# Motor_Module.net
KiCad netlist of a schematic drawn in Altium Designer
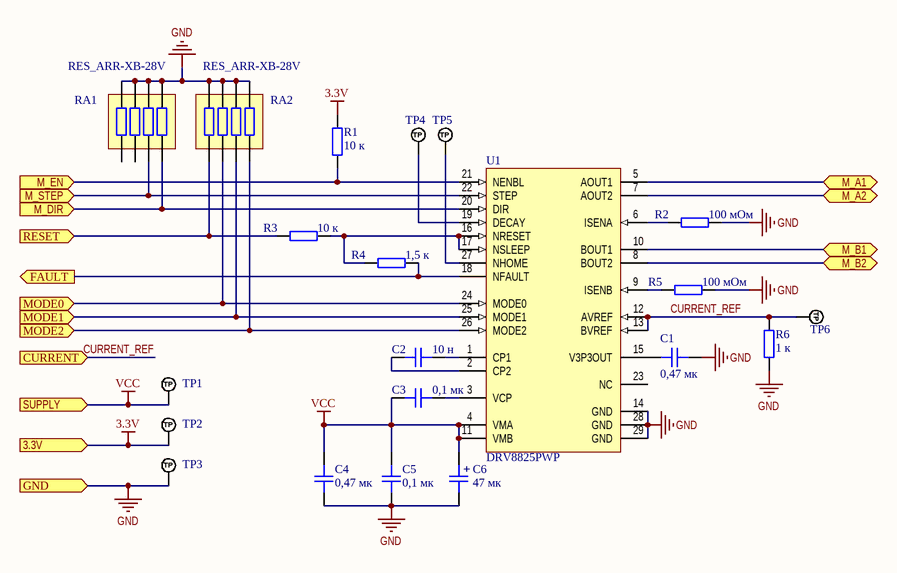
[diagram p0: Motor_Module.SchDoc]

(export (version "E")
  (design (tool "Eeschema 10.0.6"))
  (components
    (comp (ref "C1")
      (value "0,47 мк")
      (footprint "CAP_0603")
      (description "Capacitor SMD 0805")
      (libsource (lib "Schematic-Lib-PhilsLab") (part "CAP_0805"))
    )
    (comp (ref "C2")
      (value "10 н")
      (footprint "CAP_0603")
      (description "Capacitor SMD 0805")
      (libsource (lib "Schematic-Lib-PhilsLab") (part "CAP_0805"))
    )
    (comp (ref "C3")
      (value "0,1 мк")
      (footprint "CAP_0603")
      (description "Capacitor SMD 0805")
      (fields (field (name "VOLTAGE") "50"))
      (libsource (lib "Schematic-Lib-PhilsLab") (part "CAP_0805"))
    )
    (comp (ref "C4")
      (value "0,47 мк")
      (footprint "CAP_0805")
      (description "Capacitor SMD 0805")
      (fields (field (name "VOLTAGE") "50"))
      (libsource (lib "Schematic-Lib-PhilsLab") (part "CAP_0805"))
    )
    (comp (ref "C5")
      (value "0,1 мк")
      (footprint "CAP_0805")
      (description "Capacitor SMD 0805")
      (fields (field (name "VOLTAGE") "50"))
      (libsource (lib "Schematic-Lib-PhilsLab") (part "CAP_0805"))
    )
    (comp (ref "C6")
      (value "47 мк")
      (footprint "CAP_AE_SMD_D6MM3_H5M55")
      (description "Capacitor SMD Aluminium Electrolytic 6.3mm Diameter 5.5mm Height")
      (fields (field (name "VOLTAGE") "50"))
      (libsource (lib "Schematic-Lib-PhilsLab") (part "CAP_ALEL_6.3x5.5"))
    )
    (comp (ref "R1")
      (value "10 к")
      (footprint "RES_0603")
      (description "Resistor SMD 0805")
      (libsource (lib "Schematic-Lib-PhilsLab") (part "RES_0805"))
    )
    (comp (ref "R2")
      (value "100 мОм")
      (footprint "RES_1206")
      (description "Resistor SMD 1206")
      (libsource (lib "Schematic-Lib-PhilsLab") (part "RES_1206"))
    )
    (comp (ref "R3")
      (value "10 к")
      (footprint "RES_0603")
      (description "Resistor SMD 0805")
      (libsource (lib "Schematic-Lib-PhilsLab") (part "RES_0805"))
    )
    (comp (ref "R4")
      (value "1,5 к")
      (footprint "RES_0603")
      (description "Resistor SMD 0805")
      (libsource (lib "Schematic-Lib-PhilsLab") (part "RES_0805"))
    )
    (comp (ref "R5")
      (value "100 мОм")
      (footprint "RES_1206")
      (description "Resistor SMD 1206")
      (libsource (lib "Schematic-Lib-PhilsLab") (part "RES_1206"))
    )
    (comp (ref "R6")
      (value "1 к")
      (footprint "RES_0603")
      (description "Resistor SMD 0805")
      (libsource (lib "Schematic-Lib-PhilsLab") (part "RES_0805"))
    )
    (comp (ref "RA1")
      (value "RES_ARR-XB-28V")
      (footprint "EXB-28V")
      (description "Resistor Array 0402 4 Elements Panasonic EXB-28V")
      (fields (field (name "MANUFACTURER") "Panasonic"))
      (libsource (lib "Schematic-Lib-PhilsLab") (part "RES_ARR-XB-28V"))
    )
    (comp (ref "RA2")
      (value "RES_ARR-XB-28V")
      (footprint "EXB-28V")
      (description "Resistor Array 0402 4 Elements Panasonic EXB-28V")
      (fields (field (name "MANUFACTURER") "Panasonic"))
      (libsource (lib "Schematic-Lib-PhilsLab") (part "RES_ARR-XB-28V"))
    )
    (comp (ref "TP1")
      (value "SUP")
      (footprint "PAD_RND_1MM")
      (description "Test Point Round 1mm (NO BOM)")
      (libsource (lib "Schematic-Lib-PhilsLab") (part "TEST_POINT_RND_1MM"))
    )
    (comp (ref "TP2")
      (value "SUP")
      (footprint "PAD_RND_1MM")
      (description "Test Point Round 1mm (NO BOM)")
      (libsource (lib "Schematic-Lib-PhilsLab") (part "TEST_POINT_RND_1MM"))
    )
    (comp (ref "TP3")
      (value "GND")
      (footprint "PAD_RND_1MM")
      (description "Test Point Round 1mm (NO BOM)")
      (libsource (lib "Schematic-Lib-PhilsLab") (part "TEST_POINT_RND_1MM"))
    )
    (comp (ref "TP4")
      (value "DECAY")
      (footprint "PAD_RND_1MM")
      (description "Test Point Round 1mm (NO BOM)")
      (libsource (lib "Schematic-Lib-PhilsLab") (part "TEST_POINT_RND_1MM"))
    )
    (comp (ref "TP5")
      (value "NHOME")
      (footprint "PAD_RND_1MM")
      (description "Test Point Round 1mm (NO BOM)")
      (libsource (lib "Schematic-Lib-PhilsLab") (part "TEST_POINT_RND_1MM"))
    )
    (comp (ref "TP6")
      (value "CURRENT")
      (footprint "PAD_RND_1MM")
      (description "Test Point Round 1mm (NO BOM)")
      (libsource (lib "Schematic-Lib-PhilsLab") (part "TEST_POINT_RND_1MM"))
    )
    (comp (ref "U1")
      (value "DRV8825PWP")
      (footprint "PWP0028C_L")
      (libsource (lib "Altium Content Vault") (part "TI-DRV882XPWP28-XXXXXXXXXTP"))
    )
  )
  (nets
    (net (code "1") (name "/CURRENT_REF") (class "Default")
      (node (ref "R6") (pin "1") (pinfunction "1_1") (pintype "passive"))
      (node (ref "TP6") (pin "1") (pinfunction "TP_1") (pintype "passive"))
      (node (ref "U1") (pin "12") (pinfunction "AVREF_12") (pintype "input"))
      (node (ref "U1") (pin "13") (pinfunction "BVREF_13") (pintype "input"))
    )
    (net (code "2") (name "/FAULT") (class "Default")
      (node (ref "R4") (pin "1") (pinfunction "1_1") (pintype "passive"))
      (node (ref "U1") (pin "18") (pinfunction "NFAULT_18") (pintype "open_collector"))
    )
    (net (code "3") (name "/MODE0") (class "Default")
      (node (ref "RA2") (pin "2") (pinfunction "2_2") (pintype "passive"))
      (node (ref "U1") (pin "24") (pinfunction "MODE0_24") (pintype "input"))
    )
    (net (code "4") (name "/MODE1") (class "Default")
      (node (ref "RA2") (pin "3") (pinfunction "3_3") (pintype "passive"))
      (node (ref "U1") (pin "25") (pinfunction "MODE1_25") (pintype "input"))
    )
    (net (code "5") (name "/MODE2") (class "Default")
      (node (ref "RA2") (pin "4") (pinfunction "4_4") (pintype "passive"))
      (node (ref "U1") (pin "26") (pinfunction "MODE2_26") (pintype "input"))
    )
    (net (code "6") (name "/M_A1") (class "Default")
      (node (ref "U1") (pin "5") (pinfunction "AOUT1_5") (pintype "tri_state"))
    )
    (net (code "7") (name "/M_A2") (class "Default")
      (node (ref "U1") (pin "7") (pinfunction "AOUT2_7") (pintype "tri_state"))
    )
    (net (code "8") (name "/M_B1") (class "Default")
      (node (ref "U1") (pin "10") (pinfunction "BOUT1_10") (pintype "tri_state"))
    )
    (net (code "9") (name "/M_B2") (class "Default")
      (node (ref "U1") (pin "8") (pinfunction "BOUT2_8") (pintype "tri_state"))
    )
    (net (code "10") (name "/M_DIR") (class "Default")
      (node (ref "RA1") (pin "4") (pinfunction "4_4") (pintype "passive"))
      (node (ref "U1") (pin "20") (pinfunction "DIR_20") (pintype "input"))
    )
    (net (code "11") (name "/M_EN") (class "Default")
      (node (ref "R1") (pin "2") (pinfunction "2_2") (pintype "passive"))
      (node (ref "U1") (pin "21") (pinfunction "NENBL_21") (pintype "input"))
    )
    (net (code "12") (name "/M_STEP") (class "Default")
      (node (ref "RA1") (pin "3") (pinfunction "3_3") (pintype "passive"))
      (node (ref "U1") (pin "22") (pinfunction "STEP_22") (pintype "input"))
    )
    (net (code "13") (name "/RESET") (class "Default")
      (node (ref "R3") (pin "2") (pinfunction "2_2") (pintype "passive"))
      (node (ref "RA2") (pin "1") (pinfunction "1_1") (pintype "passive"))
    )
    (net (code "14") (name "3.3V") (class "Default")
      (node (ref "R1") (pin "1") (pinfunction "1_1") (pintype "passive"))
      (node (ref "TP2") (pin "1") (pinfunction "TP_1") (pintype "passive"))
    )
    (net (code "15") (name "GND") (class "Default")
      (node (ref "C1") (pin "2") (pinfunction "2_2") (pintype "passive"))
      (node (ref "C4") (pin "2") (pinfunction "2_2") (pintype "passive"))
      (node (ref "C5") (pin "2") (pinfunction "2_2") (pintype "passive"))
      (node (ref "C6") (pin "2") (pinfunction "2_2") (pintype "passive"))
      (node (ref "R2") (pin "2") (pinfunction "2_2") (pintype "passive"))
      (node (ref "R5") (pin "2") (pinfunction "2_2") (pintype "passive"))
      (node (ref "R6") (pin "2") (pinfunction "2_2") (pintype "passive"))
      (node (ref "RA1") (pin "5") (pinfunction "5_5") (pintype "passive"))
      (node (ref "RA1") (pin "6") (pinfunction "6_6") (pintype "passive"))
      (node (ref "RA1") (pin "7") (pinfunction "7_7") (pintype "passive"))
      (node (ref "RA1") (pin "8") (pinfunction "8_8") (pintype "passive"))
      (node (ref "RA2") (pin "5") (pinfunction "5_5") (pintype "passive"))
      (node (ref "RA2") (pin "6") (pinfunction "6_6") (pintype "passive"))
      (node (ref "RA2") (pin "7") (pinfunction "7_7") (pintype "passive"))
      (node (ref "RA2") (pin "8") (pinfunction "8_8") (pintype "passive"))
      (node (ref "TP3") (pin "1") (pinfunction "TP_1") (pintype "passive"))
      (node (ref "U1") (pin "14") (pinfunction "GND_14") (pintype "power_in"))
      (node (ref "U1") (pin "28") (pinfunction "GND_28") (pintype "power_in"))
      (node (ref "U1") (pin "29") (pinfunction "GND_29") (pintype "power_in"))
    )
    (net (code "16") (name "Net-(TP4-TP)") (class "Default")
      (node (ref "TP4") (pin "1") (pinfunction "TP_1") (pintype "passive"))
      (node (ref "U1") (pin "19") (pinfunction "DECAY_19") (pintype "input"))
    )
    (net (code "17") (name "Net-(TP5-TP)") (class "Default")
      (node (ref "TP5") (pin "1") (pinfunction "TP_1") (pintype "passive"))
      (node (ref "U1") (pin "27") (pinfunction "NHOME_27") (pintype "open_collector"))
    )
    (net (code "18") (name "Net-(U1-CP1)") (class "Default")
      (node (ref "C2") (pin "1") (pinfunction "1_1") (pintype "passive"))
      (node (ref "U1") (pin "1") (pinfunction "CP1_1") (pintype "passive"))
    )
    (net (code "19") (name "Net-(U1-CP2)") (class "Default")
      (node (ref "C2") (pin "2") (pinfunction "2_2") (pintype "passive"))
      (node (ref "U1") (pin "2") (pinfunction "CP2_2") (pintype "passive"))
    )
    (net (code "20") (name "Net-(U1-ISENA)") (class "Default")
      (node (ref "R2") (pin "1") (pinfunction "1_1") (pintype "passive"))
      (node (ref "U1") (pin "6") (pinfunction "ISENA_6") (pintype "input"))
    )
    (net (code "21") (name "Net-(U1-ISENB)") (class "Default")
      (node (ref "R5") (pin "1") (pinfunction "1_1") (pintype "passive"))
      (node (ref "U1") (pin "9") (pinfunction "ISENB_9") (pintype "input"))
    )
    (net (code "22") (name "Net-(U1-NRESET)") (class "Default")
      (node (ref "R3") (pin "1") (pinfunction "1_1") (pintype "passive"))
      (node (ref "R4") (pin "2") (pinfunction "2_2") (pintype "passive"))
      (node (ref "U1") (pin "16") (pinfunction "NRESET_16") (pintype "input"))
      (node (ref "U1") (pin "17") (pinfunction "NSLEEP_17") (pintype "input"))
    )
    (net (code "23") (name "Net-(U1-V3P3OUT)") (class "Default")
      (node (ref "C1") (pin "1") (pinfunction "1_1") (pintype "passive"))
      (node (ref "U1") (pin "15") (pinfunction "V3P3OUT_15") (pintype "power_in"))
    )
    (net (code "24") (name "Net-(U1-VCP)") (class "Default")
      (node (ref "C3") (pin "2") (pinfunction "2_2") (pintype "passive"))
      (node (ref "U1") (pin "3") (pinfunction "VCP_3") (pintype "passive"))
    )
    (net (code "25") (name "VCC") (class "Default")
      (node (ref "C3") (pin "1") (pinfunction "1_1") (pintype "passive"))
      (node (ref "C4") (pin "1") (pinfunction "1_1") (pintype "passive"))
      (node (ref "C5") (pin "1") (pinfunction "1_1") (pintype "passive"))
      (node (ref "C6") (pin "1") (pinfunction "1_1") (pintype "passive"))
      (node (ref "TP1") (pin "1") (pinfunction "TP_1") (pintype "passive"))
      (node (ref "U1") (pin "11") (pinfunction "VMB_11") (pintype "power_in"))
      (node (ref "U1") (pin "4") (pinfunction "VMA_4") (pintype "power_in"))
    )
    (net (code "26") (name "unconnected-(RA1-Pad1)") (class "Default")
      (node (ref "RA1") (pin "1") (pinfunction "1_1") (pintype "passive"))
    )
    (net (code "27") (name "unconnected-(RA1-Pad2)") (class "Default")
      (node (ref "RA1") (pin "2") (pinfunction "2_2") (pintype "passive"))
    )
    (net (code "28") (name "unconnected-(U1-NC-Pad23)") (class "Default")
      (node (ref "U1") (pin "23") (pinfunction "NC_23") (pintype "passive"))
    )
  )
)
